# stm8-accelerometer_-1.net
KiCad netlist of a schematic drawn in EAGLE
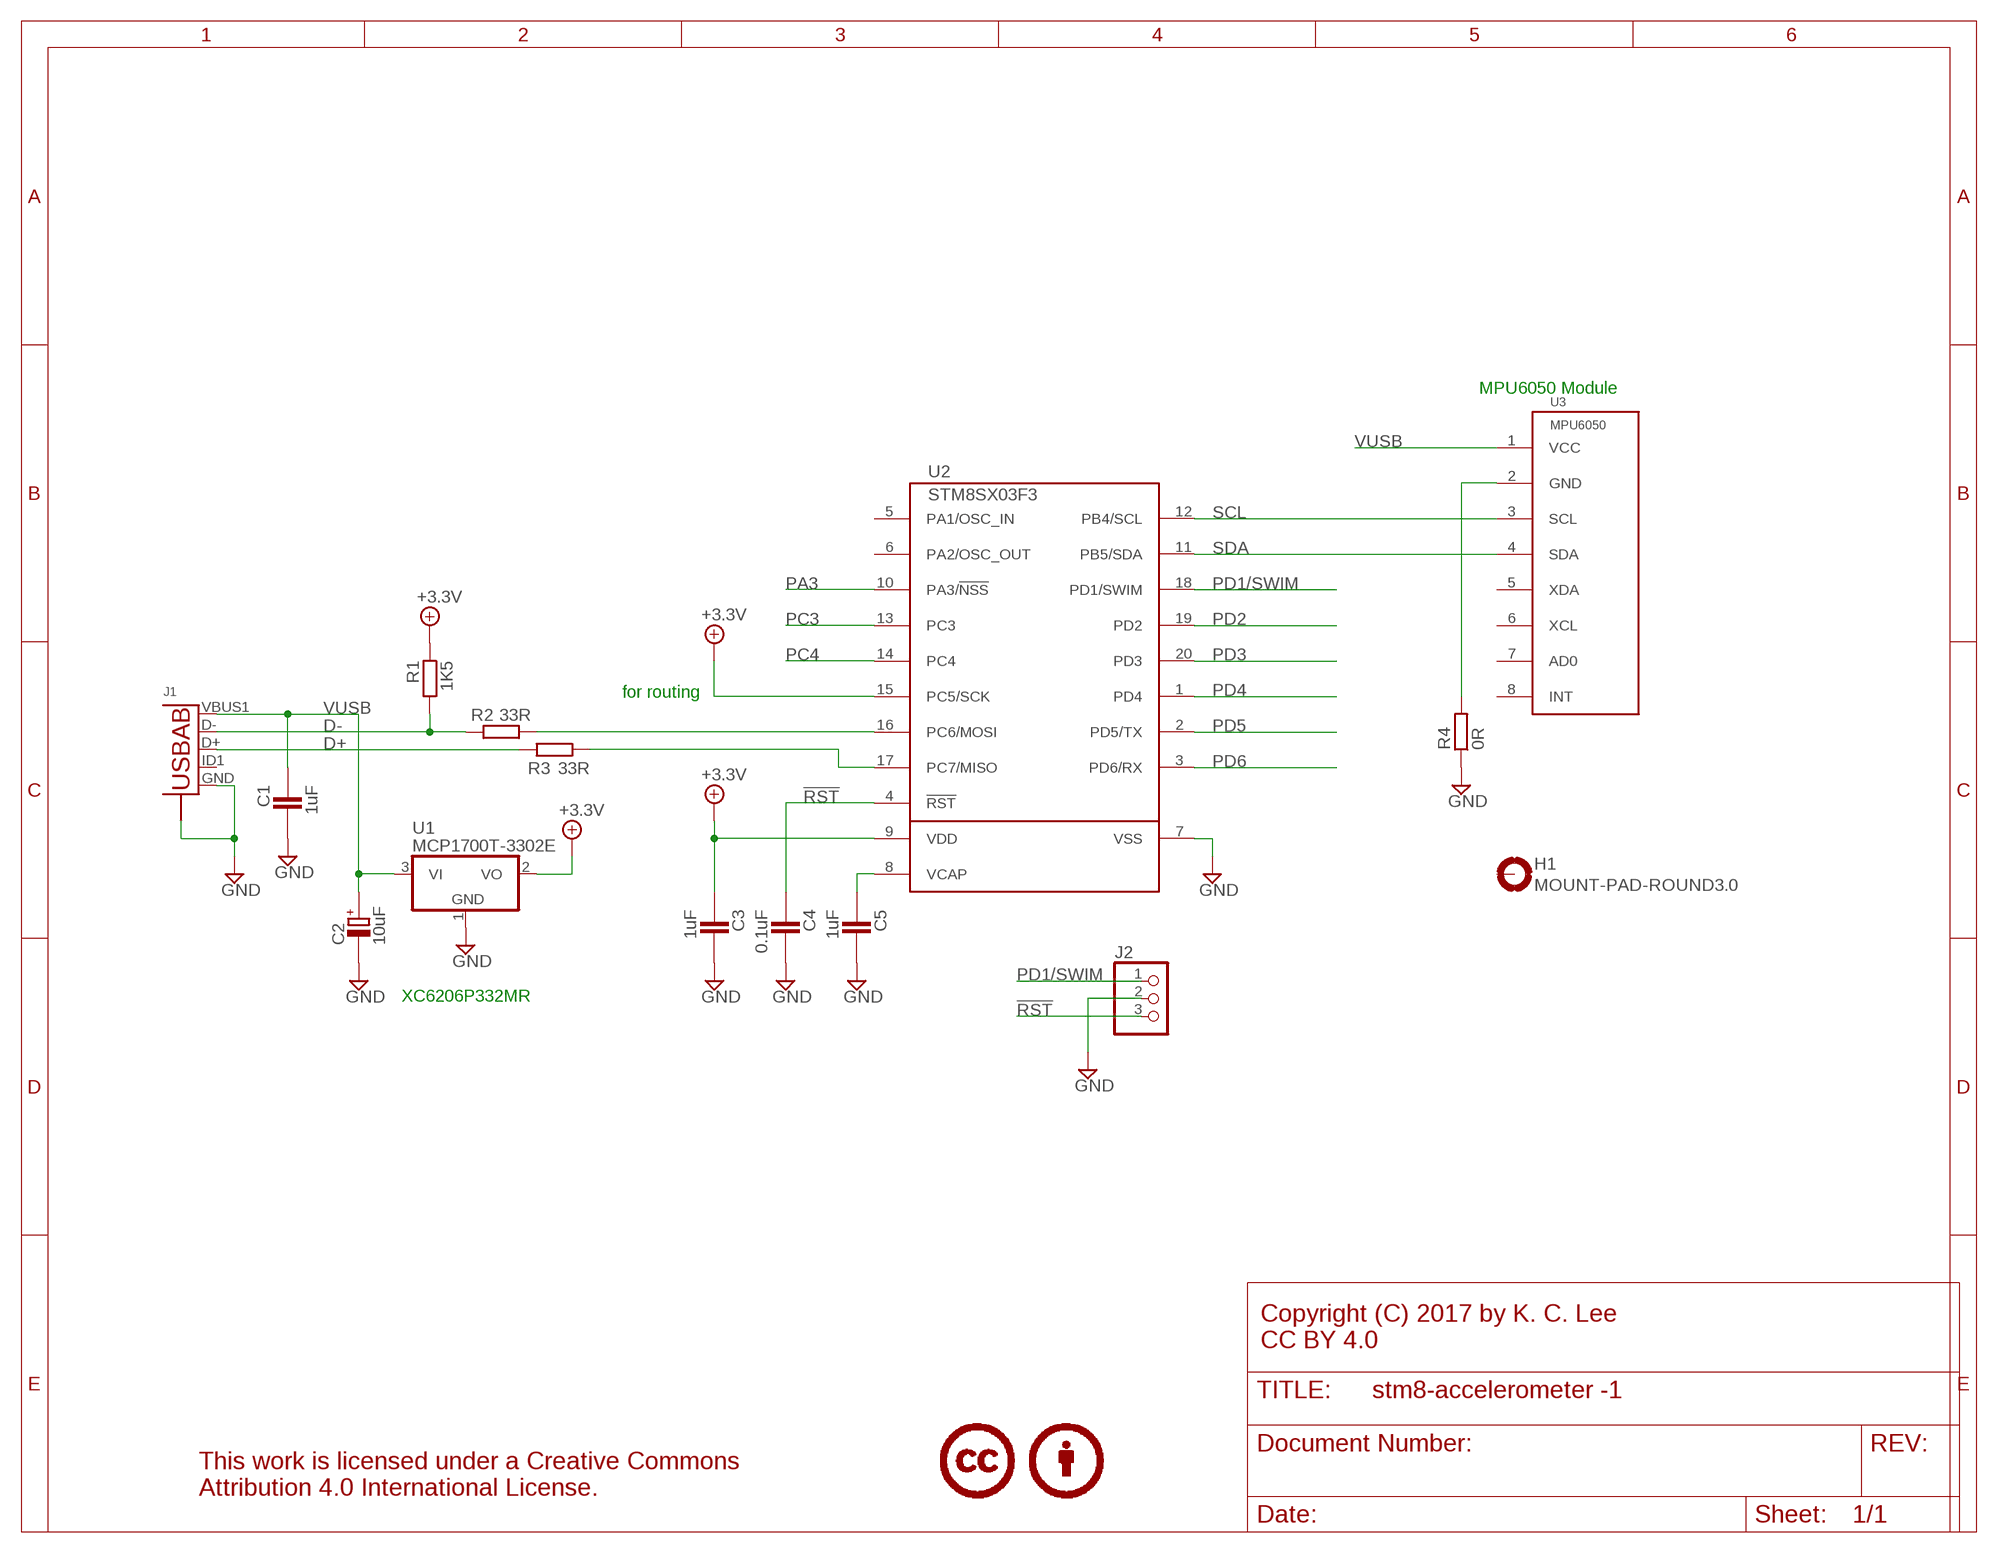
[diagram p0: schematic, sheet 1]

(export (version "E")
  (design (tool "Eeschema 10.0.6"))
  (components
    (comp (ref "C1")
      (value "1uF")
      (footprint "eagle-import:CAPC1608X92N")
      (fields (field (name "PARTNO") "NC 0805"))
      (libsource (lib "eagle-import") (part "CAPACITOR_0603"))
    )
    (comp (ref "C2")
      (value "10uF")
      (footprint "eagle-import:CAPMP6032X280N")
      (fields (field (name "PARTNO") "1uF X7R 0603"))
      (libsource (lib "eagle-import") (part "POLARISED_C_CASE"))
    )
    (comp (ref "C3")
      (value "1uF")
      (footprint "eagle-import:CAPC1608X92N")
      (fields (field (name "PARTNO") "1uF X7R 0603"))
      (libsource (lib "eagle-import") (part "CAPACITOR_0603"))
    )
    (comp (ref "C4")
      (value "0.1uF")
      (footprint "eagle-import:CAPC1608X92N")
      (fields (field (name "PARTNO") "1uF X7R 0603"))
      (libsource (lib "eagle-import") (part "CAPACITOR_0603"))
    )
    (comp (ref "C5")
      (value "1uF")
      (footprint "eagle-import:CAPC1608X92N")
      (fields (field (name "PARTNO") "1uF X7R 0603"))
      (libsource (lib "eagle-import") (part "CAPACITOR_0603"))
    )
    (comp (ref "H1")
      (value "MOUNT-PAD-ROUND3.0")
      (footprint "eagle-import:3,0-PAD")
      (libsource (lib "eagle-import") (part "MOUNT-PAD-ROUND3.0"))
    )
    (comp (ref "J1")
      (value "USB-ABBG-ORG")
      (footprint "eagle-import:USB-AB-MICRO-SMD_V03_SMT")
      (libsource (lib "eagle-import") (part "USB-ABBG-ORG"))
    )
    (comp (ref "J2")
      (value "PINHD-1X3_2.54")
      (footprint "eagle-import:1X03")
      (libsource (lib "eagle-import") (part "PINHD-1X3_2.54"))
    )
    (comp (ref "LICENSE1")
      (value "CC-BY50%")
      (footprint "eagle-import:CC-BY-50")
      (libsource (lib "eagle-import") (part "CC-BY50%"))
    )
    (comp (ref "R1")
      (value "1K5")
      (footprint "eagle-import:RESC1608X55N")
      (fields (field (name "PARTNO") "1K5 0603"))
      (libsource (lib "eagle-import") (part "RESISTOR_0603"))
    )
    (comp (ref "R2")
      (value "33R")
      (footprint "eagle-import:RESC1608X55N")
      (fields (field (name "PARTNO") "47R 0603"))
      (libsource (lib "eagle-import") (part "RESISTOR_0603"))
    )
    (comp (ref "R3")
      (value "33R")
      (footprint "eagle-import:RESC1608X55N")
      (fields (field (name "PARTNO") "47R 0603"))
      (libsource (lib "eagle-import") (part "RESISTOR_0603"))
    )
    (comp (ref "R4")
      (value "0R")
      (footprint "eagle-import:RESC3115X70N")
      (libsource (lib "eagle-import") (part "RESISTOR_1206"))
    )
    (comp (ref "U1")
      (value "MCP1700T-3302E")
      (footprint "eagle-import:SOT95P280X135-3N")
      (fields (field (name "PARTNO") "MCP1700T-3302E/TT"))
      (libsource (lib "eagle-import") (part "MCP1700/TT"))
    )
    (comp (ref "U2")
      (value "STM8SX03F3")
      (footprint "eagle-import:TSSOP20")
      (libsource (lib "eagle-import") (part "STM8SX03F3"))
    )
    (comp (ref "U3")
      (value "MPU6050")
      (footprint "eagle-import:MPU6050")
      (libsource (lib "eagle-import") (part "MPU6050"))
    )
  )
  (nets
    (net (code "1") (name "+3.3V") (class "Default")
      (node (ref "C3") (pin "1") (pinfunction "1_1") (pintype "passive"))
      (node (ref "R1") (pin "1") (pinfunction "1_1") (pintype "passive"))
      (node (ref "U1") (pin "2") (pinfunction "VO_2") (pintype "passive"))
      (node (ref "U2") (pin "15") (pinfunction "PC5/SCK_15") (pintype "bidirectional"))
      (node (ref "U2") (pin "9") (pinfunction "VDD_9") (pintype "input"))
    )
    (net (code "2") (name "/D+") (class "Default")
      (node (ref "J1") (pin "D+") (pinfunction "D+_D+") (pintype "bidirectional"))
      (node (ref "R3") (pin "1") (pinfunction "1_1") (pintype "passive"))
    )
    (net (code "3") (name "/D-") (class "Default")
      (node (ref "J1") (pin "D-") (pinfunction "D-_D-") (pintype "bidirectional"))
      (node (ref "R1") (pin "2") (pinfunction "2_2") (pintype "passive"))
      (node (ref "R2") (pin "1") (pinfunction "1_1") (pintype "passive"))
    )
    (net (code "4") (name "/PA3") (class "Default")
      (node (ref "U2") (pin "10") (pinfunction "PA3/~{NSS}_10") (pintype "bidirectional"))
    )
    (net (code "5") (name "/PC3") (class "Default")
      (node (ref "U2") (pin "13") (pinfunction "PC3_13") (pintype "bidirectional"))
    )
    (net (code "6") (name "/PC4") (class "Default")
      (node (ref "U2") (pin "14") (pinfunction "PC4_14") (pintype "bidirectional"))
    )
    (net (code "7") (name "/PD1{slash}SWIM") (class "Default")
      (node (ref "J2") (pin "1") (pinfunction "1_1") (pintype "passive"))
      (node (ref "U2") (pin "18") (pinfunction "PD1/SWIM_18") (pintype "input"))
    )
    (net (code "8") (name "/PD2") (class "Default")
      (node (ref "U2") (pin "19") (pinfunction "PD2_19") (pintype "bidirectional"))
    )
    (net (code "9") (name "/PD3") (class "Default")
      (node (ref "U2") (pin "20") (pinfunction "PD3_20") (pintype "bidirectional"))
    )
    (net (code "10") (name "/PD4") (class "Default")
      (node (ref "U2") (pin "1") (pinfunction "PD4_1") (pintype "bidirectional"))
    )
    (net (code "11") (name "/PD5") (class "Default")
      (node (ref "U2") (pin "2") (pinfunction "PD5/TX_2") (pintype "bidirectional"))
    )
    (net (code "12") (name "/PD6") (class "Default")
      (node (ref "U2") (pin "3") (pinfunction "PD6/RX_3") (pintype "bidirectional"))
    )
    (net (code "13") (name "/SCL") (class "Default")
      (node (ref "U2") (pin "12") (pinfunction "PB4/SCL_12") (pintype "bidirectional"))
      (node (ref "U3") (pin "3") (pinfunction "SCL_3") (pintype "bidirectional"))
    )
    (net (code "14") (name "/SDA") (class "Default")
      (node (ref "U2") (pin "11") (pinfunction "PB5/SDA_11") (pintype "bidirectional"))
      (node (ref "U3") (pin "4") (pinfunction "SDA_4") (pintype "bidirectional"))
    )
    (net (code "15") (name "/VUSB") (class "Default")
      (node (ref "C1") (pin "1") (pinfunction "1_1") (pintype "passive"))
      (node (ref "C2") (pin "+") (pinfunction "+_+") (pintype "passive"))
      (node (ref "J1") (pin "VBUS1") (pinfunction "VBUS_VBUS1") (pintype "bidirectional"))
      (node (ref "U1") (pin "3") (pinfunction "VI_3") (pintype "input"))
      (node (ref "U3") (pin "1") (pinfunction "VCC_1") (pintype "bidirectional"))
    )
    (net (code "16") (name "/~{RST}") (class "Default")
      (node (ref "C4") (pin "1") (pinfunction "1_1") (pintype "passive"))
      (node (ref "J2") (pin "3") (pinfunction "3_3") (pintype "passive"))
      (node (ref "U2") (pin "4") (pinfunction "~{RST}_4") (pintype "input"))
    )
    (net (code "17") (name "GND") (class "Default")
      (node (ref "C1") (pin "2") (pinfunction "2_2") (pintype "passive"))
      (node (ref "C2") (pin "-") (pinfunction "-_-") (pintype "passive"))
      (node (ref "C3") (pin "2") (pinfunction "2_2") (pintype "passive"))
      (node (ref "C4") (pin "2") (pinfunction "2_2") (pintype "passive"))
      (node (ref "C5") (pin "2") (pinfunction "2_2") (pintype "passive"))
      (node (ref "J1") (pin "GND") (pinfunction "GND_GND") (pintype "bidirectional"))
      (node (ref "J1") (pin "S1") (pinfunction "S_S1") (pintype "bidirectional"))
      (node (ref "J1") (pin "S2") (pinfunction "S_S2") (pintype "bidirectional"))
      (node (ref "J1") (pin "S3") (pinfunction "S_S3") (pintype "bidirectional"))
      (node (ref "J1") (pin "S4") (pinfunction "S_S4") (pintype "bidirectional"))
      (node (ref "J2") (pin "2") (pinfunction "2_2") (pintype "passive"))
      (node (ref "R4") (pin "1") (pinfunction "1_1") (pintype "passive"))
      (node (ref "U1") (pin "1") (pinfunction "GND_1") (pintype "passive"))
      (node (ref "U2") (pin "7") (pinfunction "VSS_7") (pintype "input"))
    )
    (net (code "18") (name "Net-(U2-PC6{slash}MOSI)") (class "Default")
      (node (ref "R2") (pin "2") (pinfunction "2_2") (pintype "passive"))
      (node (ref "U2") (pin "16") (pinfunction "PC6/MOSI_16") (pintype "bidirectional"))
    )
    (net (code "19") (name "Net-(U2-PC7{slash}MISO)") (class "Default")
      (node (ref "R3") (pin "2") (pinfunction "2_2") (pintype "passive"))
      (node (ref "U2") (pin "17") (pinfunction "PC7/MISO_17") (pintype "bidirectional"))
    )
    (net (code "20") (name "Net-(U2-VCAP)") (class "Default")
      (node (ref "C5") (pin "1") (pinfunction "1_1") (pintype "passive"))
      (node (ref "U2") (pin "8") (pinfunction "VCAP_8") (pintype "input"))
    )
    (net (code "21") (name "Net-(U3-GND)") (class "Default")
      (node (ref "R4") (pin "2") (pinfunction "2_2") (pintype "passive"))
      (node (ref "U3") (pin "2") (pinfunction "GND_2") (pintype "bidirectional"))
    )
    (net (code "22") (name "unconnected-(H1-MOUNT-PadB3,0)") (class "Default")
      (node (ref "H1") (pin "B3,0") (pinfunction "MOUNT_B3,0") (pintype "passive"))
    )
    (net (code "23") (name "unconnected-(J1-USBID-PadID1)") (class "Default")
      (node (ref "J1") (pin "ID1") (pinfunction "USBID_ID1") (pintype "bidirectional"))
    )
    (net (code "24") (name "unconnected-(U2-PA1{slash}OSC_IN-Pad5)") (class "Default")
      (node (ref "U2") (pin "5") (pinfunction "PA1/OSC_IN_5") (pintype "input"))
    )
    (net (code "25") (name "unconnected-(U2-PA2{slash}OSC_OUT-Pad6)") (class "Default")
      (node (ref "U2") (pin "6") (pinfunction "PA2/OSC_OUT_6") (pintype "output"))
    )
    (net (code "26") (name "unconnected-(U3-AD0-Pad7)") (class "Default")
      (node (ref "U3") (pin "7") (pinfunction "AD0_7") (pintype "bidirectional"))
    )
    (net (code "27") (name "unconnected-(U3-INT-Pad8)") (class "Default")
      (node (ref "U3") (pin "8") (pinfunction "INT_8") (pintype "bidirectional"))
    )
    (net (code "28") (name "unconnected-(U3-XCL-Pad6)") (class "Default")
      (node (ref "U3") (pin "6") (pinfunction "XCL_6") (pintype "bidirectional"))
    )
    (net (code "29") (name "unconnected-(U3-XDA-Pad5)") (class "Default")
      (node (ref "U3") (pin "5") (pinfunction "XDA_5") (pintype "bidirectional"))
    )
  )
)
